# transponder_2018_v3.net
KiCad netlist of a schematic drawn in EAGLE
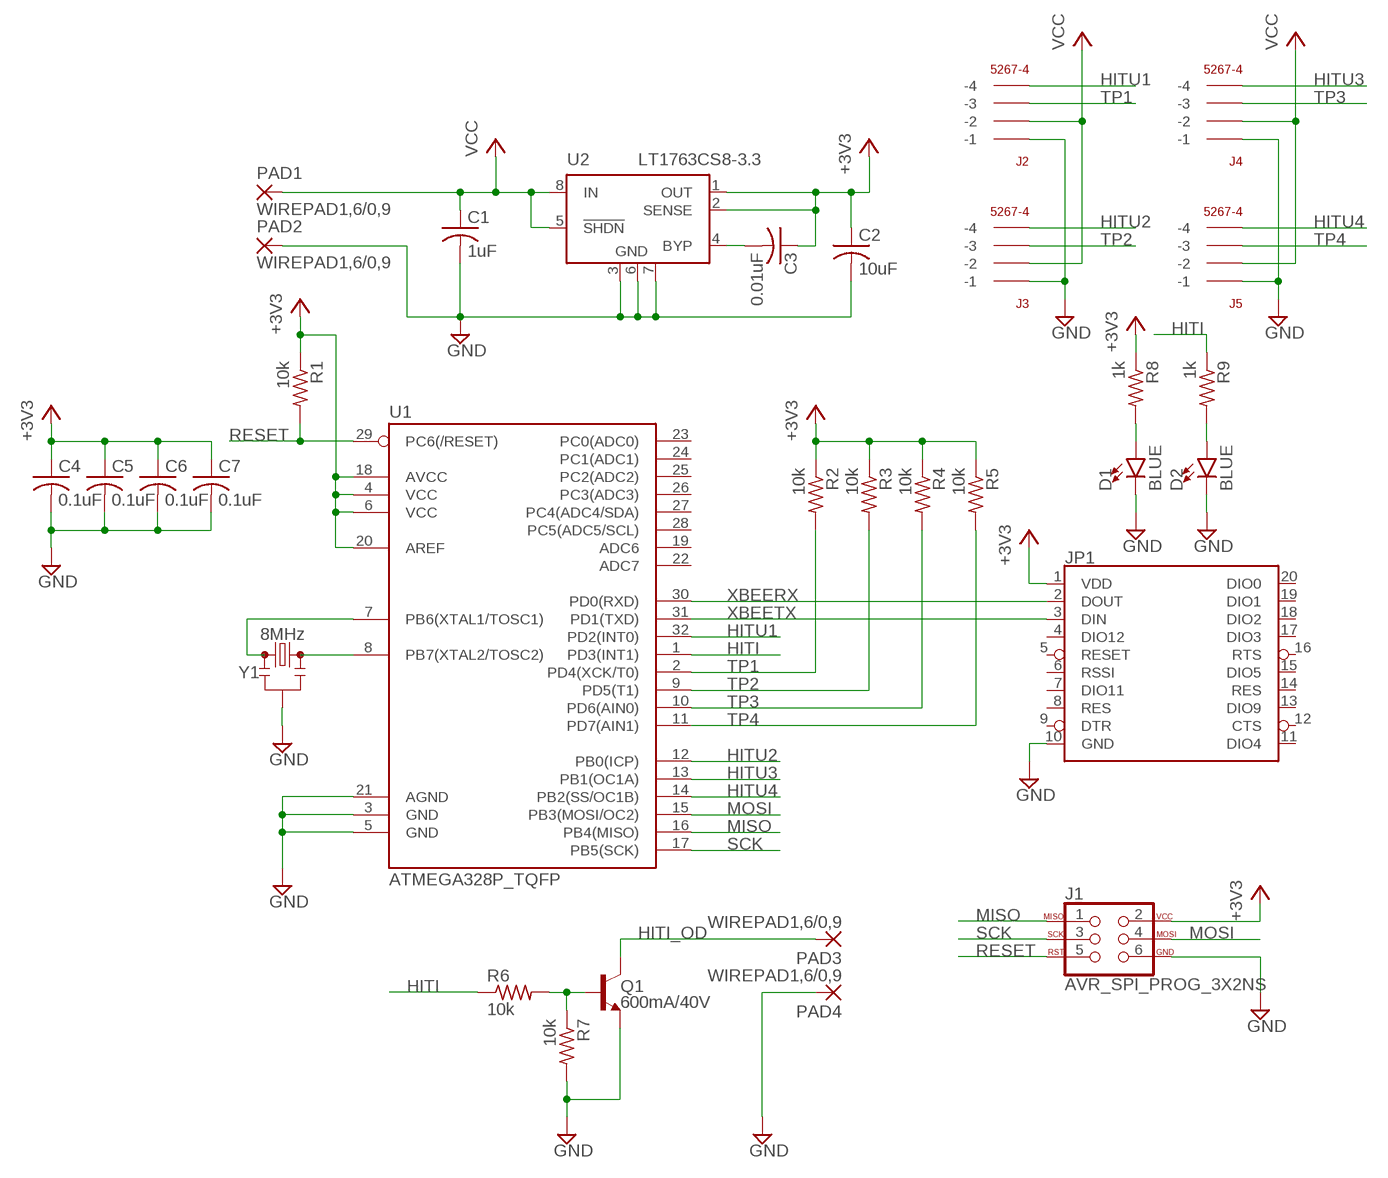
[diagram p0: schematic, sheet 1]

(export (version "E")
  (design (tool "Eeschema 10.0.6"))
  (components
    (comp (ref "C1")
      (value "1uF")
      (footprint "eagle-import:C0603")
      (libsource (lib "eagle-import") (part "C-USC0603"))
    )
    (comp (ref "C2")
      (value "10uF")
      (footprint "eagle-import:C1206")
      (libsource (lib "eagle-import") (part "C-USC1206"))
    )
    (comp (ref "C3")
      (value "0.01uF")
      (footprint "eagle-import:C0603")
      (libsource (lib "eagle-import") (part "C-USC0603"))
    )
    (comp (ref "C4")
      (value "0.1uF")
      (footprint "eagle-import:C0603")
      (libsource (lib "eagle-import") (part "C-USC0603"))
    )
    (comp (ref "C5")
      (value "0.1uF")
      (footprint "eagle-import:C0603")
      (libsource (lib "eagle-import") (part "C-USC0603"))
    )
    (comp (ref "C6")
      (value "0.1uF")
      (footprint "eagle-import:C0603")
      (libsource (lib "eagle-import") (part "C-USC0603"))
    )
    (comp (ref "C7")
      (value "0.1uF")
      (footprint "eagle-import:C0603")
      (libsource (lib "eagle-import") (part "C-USC0603"))
    )
    (comp (ref "D1")
      (value "BLUE")
      (footprint "eagle-import:LED-0603")
      (libsource (lib "eagle-import") (part "LED-BLUE0603"))
    )
    (comp (ref "D2")
      (value "BLUE")
      (footprint "eagle-import:LED-0603")
      (libsource (lib "eagle-import") (part "LED-BLUE0603"))
    )
    (comp (ref "J1")
      (value "AVR_SPI_PROG_3X2NS")
      (footprint "eagle-import:2X3-NS")
      (libsource (lib "eagle-import") (part "AVR_SPI_PROG_3X2NS"))
    )
    (comp (ref "J2")
      (value "5267-4")
      (footprint "eagle-import:5267-4")
      (libsource (lib "eagle-import") (part "5267-4"))
    )
    (comp (ref "J3")
      (value "5267-4")
      (footprint "eagle-import:5267-4")
      (libsource (lib "eagle-import") (part "5267-4"))
    )
    (comp (ref "J4")
      (value "5267-4")
      (footprint "eagle-import:5267-4")
      (libsource (lib "eagle-import") (part "5267-4"))
    )
    (comp (ref "J5")
      (value "5267-4")
      (footprint "eagle-import:5267-4")
      (libsource (lib "eagle-import") (part "5267-4"))
    )
    (comp (ref "JP1")
      (value "XBEESMD")
      (footprint "eagle-import:XBEE-SMD")
      (libsource (lib "eagle-import") (part "XBEESMD"))
    )
    (comp (ref "PAD1")
      (value "WIREPAD1,6/0,9")
      (footprint "eagle-import:1,6_0,9")
      (libsource (lib "eagle-import") (part "WIREPAD1,6/0,9"))
    )
    (comp (ref "PAD2")
      (value "WIREPAD1,6/0,9")
      (footprint "eagle-import:1,6_0,9")
      (libsource (lib "eagle-import") (part "WIREPAD1,6/0,9"))
    )
    (comp (ref "PAD3")
      (value "WIREPAD1,6/0,9")
      (footprint "eagle-import:1,6_0,9")
      (libsource (lib "eagle-import") (part "WIREPAD1,6/0,9"))
    )
    (comp (ref "PAD4")
      (value "WIREPAD1,6/0,9")
      (footprint "eagle-import:1,6_0,9")
      (libsource (lib "eagle-import") (part "WIREPAD1,6/0,9"))
    )
    (comp (ref "Q1")
      (value "600mA/40V")
      (footprint "eagle-import:SOT23-3")
      (libsource (lib "eagle-import") (part "TRANS_NPN-MMBT2222AL"))
    )
    (comp (ref "R1")
      (value "10k")
      (footprint "eagle-import:R0603")
      (libsource (lib "eagle-import") (part "R-US_R0603"))
    )
    (comp (ref "R2")
      (value "10k")
      (footprint "eagle-import:R0603")
      (libsource (lib "eagle-import") (part "R-US_R0603"))
    )
    (comp (ref "R3")
      (value "10k")
      (footprint "eagle-import:R0603")
      (libsource (lib "eagle-import") (part "R-US_R0603"))
    )
    (comp (ref "R4")
      (value "10k")
      (footprint "eagle-import:R0603")
      (libsource (lib "eagle-import") (part "R-US_R0603"))
    )
    (comp (ref "R5")
      (value "10k")
      (footprint "eagle-import:R0603")
      (libsource (lib "eagle-import") (part "R-US_R0603"))
    )
    (comp (ref "R6")
      (value "10k")
      (footprint "eagle-import:R0603")
      (libsource (lib "eagle-import") (part "R-US_R0603"))
    )
    (comp (ref "R7")
      (value "10k")
      (footprint "eagle-import:R0603")
      (libsource (lib "eagle-import") (part "R-US_R0603"))
    )
    (comp (ref "R8")
      (value "1k")
      (footprint "eagle-import:R0603")
      (libsource (lib "eagle-import") (part "R-US_R0603"))
    )
    (comp (ref "R9")
      (value "1k")
      (footprint "eagle-import:R0603")
      (libsource (lib "eagle-import") (part "R-US_R0603"))
    )
    (comp (ref "U1")
      (value "ATMEGA328P_TQFP")
      (footprint "eagle-import:TQFP32-08")
      (libsource (lib "eagle-import") (part "ATMEGA328P_TQFP"))
    )
    (comp (ref "U2")
      (value "LT1763CS8-3.3")
      (footprint "eagle-import:SOIC8")
      (libsource (lib "eagle-import") (part "LT1763CS8-3.3"))
    )
    (comp (ref "Y1")
      (value "8MHz")
      (footprint "eagle-import:RESONATOR-SMD-3.2X1.3")
      (libsource (lib "eagle-import") (part "RESONATOR-8MHZSMD_3.2X1.3"))
    )
  )
  (nets
    (net (code "1") (name "+3V3") (class "Default")
      (node (ref "C2") (pin "1") (pinfunction "1_1") (pintype "passive"))
      (node (ref "C3") (pin "1") (pinfunction "1_1") (pintype "passive"))
      (node (ref "C4") (pin "1") (pinfunction "1_1") (pintype "passive"))
      (node (ref "C5") (pin "1") (pinfunction "1_1") (pintype "passive"))
      (node (ref "C6") (pin "1") (pinfunction "1_1") (pintype "passive"))
      (node (ref "C7") (pin "1") (pinfunction "1_1") (pintype "passive"))
      (node (ref "J1") (pin "2") (pinfunction "2_2") (pintype "passive"))
      (node (ref "JP1") (pin "1") (pinfunction "VDD_1") (pintype "power_in"))
      (node (ref "R1") (pin "1") (pinfunction "1_1") (pintype "passive"))
      (node (ref "R2") (pin "1") (pinfunction "1_1") (pintype "passive"))
      (node (ref "R3") (pin "1") (pinfunction "1_1") (pintype "passive"))
      (node (ref "R4") (pin "1") (pinfunction "1_1") (pintype "passive"))
      (node (ref "R5") (pin "1") (pinfunction "1_1") (pintype "passive"))
      (node (ref "R8") (pin "1") (pinfunction "1_1") (pintype "passive"))
      (node (ref "U1") (pin "18") (pinfunction "AVCC_18") (pintype "bidirectional"))
      (node (ref "U1") (pin "20") (pinfunction "AREF_20") (pintype "bidirectional"))
      (node (ref "U1") (pin "4") (pinfunction "VCC_4") (pintype "bidirectional"))
      (node (ref "U1") (pin "6") (pinfunction "VCC_6") (pintype "bidirectional"))
      (node (ref "U2") (pin "1") (pinfunction "OUT_1") (pintype "passive"))
      (node (ref "U2") (pin "2") (pinfunction "SENSE_2") (pintype "input"))
    )
    (net (code "2") (name "/HITI") (class "Default")
      (node (ref "R6") (pin "1") (pinfunction "1_1") (pintype "passive"))
      (node (ref "R9") (pin "1") (pinfunction "1_1") (pintype "passive"))
      (node (ref "U1") (pin "1") (pinfunction "PD3(INT1)_1") (pintype "bidirectional"))
    )
    (net (code "3") (name "/HITI_OD") (class "Default")
      (node (ref "PAD3") (pin "1") (pinfunction "P_1") (pintype "passive"))
      (node (ref "Q1") (pin "3") (pinfunction "C_3") (pintype "passive"))
    )
    (net (code "4") (name "/HITU1") (class "Default")
      (node (ref "J2") (pin "P$4") (pinfunction "-4_P$4") (pintype "bidirectional"))
      (node (ref "U1") (pin "32") (pinfunction "PD2(INT0)_32") (pintype "bidirectional"))
    )
    (net (code "5") (name "/HITU2") (class "Default")
      (node (ref "J3") (pin "P$4") (pinfunction "-4_P$4") (pintype "bidirectional"))
      (node (ref "U1") (pin "12") (pinfunction "PB0(ICP)_12") (pintype "bidirectional"))
    )
    (net (code "6") (name "/HITU3") (class "Default")
      (node (ref "J4") (pin "P$4") (pinfunction "-4_P$4") (pintype "bidirectional"))
      (node (ref "U1") (pin "13") (pinfunction "PB1(OC1A)_13") (pintype "bidirectional"))
    )
    (net (code "7") (name "/HITU4") (class "Default")
      (node (ref "J5") (pin "P$4") (pinfunction "-4_P$4") (pintype "bidirectional"))
      (node (ref "U1") (pin "14") (pinfunction "PB2(SS/OC1B)_14") (pintype "bidirectional"))
    )
    (net (code "8") (name "/MISO") (class "Default")
      (node (ref "J1") (pin "1") (pinfunction "1_1") (pintype "passive"))
      (node (ref "U1") (pin "16") (pinfunction "PB4(MISO)_16") (pintype "bidirectional"))
    )
    (net (code "9") (name "/MOSI") (class "Default")
      (node (ref "J1") (pin "4") (pinfunction "4_4") (pintype "passive"))
      (node (ref "U1") (pin "15") (pinfunction "PB3(MOSI/OC2)_15") (pintype "bidirectional"))
    )
    (net (code "10") (name "/RESET") (class "Default")
      (node (ref "J1") (pin "5") (pinfunction "5_5") (pintype "passive"))
      (node (ref "R1") (pin "2") (pinfunction "2_2") (pintype "passive"))
      (node (ref "U1") (pin "29") (pinfunction "PC6(/RESET)_29") (pintype "bidirectional"))
    )
    (net (code "11") (name "/SCK") (class "Default")
      (node (ref "J1") (pin "3") (pinfunction "3_3") (pintype "passive"))
      (node (ref "U1") (pin "17") (pinfunction "PB5(SCK)_17") (pintype "bidirectional"))
    )
    (net (code "12") (name "/TP1") (class "Default")
      (node (ref "J2") (pin "P$3") (pinfunction "-3_P$3") (pintype "bidirectional"))
      (node (ref "R2") (pin "2") (pinfunction "2_2") (pintype "passive"))
      (node (ref "U1") (pin "2") (pinfunction "PD4(XCK/T0)_2") (pintype "bidirectional"))
    )
    (net (code "13") (name "/TP2") (class "Default")
      (node (ref "J3") (pin "P$3") (pinfunction "-3_P$3") (pintype "bidirectional"))
      (node (ref "R3") (pin "2") (pinfunction "2_2") (pintype "passive"))
      (node (ref "U1") (pin "9") (pinfunction "PD5(T1)_9") (pintype "bidirectional"))
    )
    (net (code "14") (name "/TP3") (class "Default")
      (node (ref "J4") (pin "P$3") (pinfunction "-3_P$3") (pintype "bidirectional"))
      (node (ref "R4") (pin "2") (pinfunction "2_2") (pintype "passive"))
      (node (ref "U1") (pin "10") (pinfunction "PD6(AIN0)_10") (pintype "bidirectional"))
    )
    (net (code "15") (name "/TP4") (class "Default")
      (node (ref "J5") (pin "P$3") (pinfunction "-3_P$3") (pintype "bidirectional"))
      (node (ref "R5") (pin "2") (pinfunction "2_2") (pintype "passive"))
      (node (ref "U1") (pin "11") (pinfunction "PD7(AIN1)_11") (pintype "bidirectional"))
    )
    (net (code "16") (name "/XBEERX") (class "Default")
      (node (ref "JP1") (pin "2") (pinfunction "DOUT_2") (pintype "output"))
      (node (ref "U1") (pin "30") (pinfunction "PD0(RXD)_30") (pintype "bidirectional"))
    )
    (net (code "17") (name "/XBEETX") (class "Default")
      (node (ref "JP1") (pin "3") (pinfunction "DIN_3") (pintype "input"))
      (node (ref "U1") (pin "31") (pinfunction "PD1(TXD)_31") (pintype "bidirectional"))
    )
    (net (code "18") (name "GND") (class "Default")
      (node (ref "C1") (pin "2") (pinfunction "2_2") (pintype "passive"))
      (node (ref "C2") (pin "2") (pinfunction "2_2") (pintype "passive"))
      (node (ref "C4") (pin "2") (pinfunction "2_2") (pintype "passive"))
      (node (ref "C5") (pin "2") (pinfunction "2_2") (pintype "passive"))
      (node (ref "C6") (pin "2") (pinfunction "2_2") (pintype "passive"))
      (node (ref "C7") (pin "2") (pinfunction "2_2") (pintype "passive"))
      (node (ref "D1") (pin "C") (pinfunction "C_C") (pintype "passive"))
      (node (ref "D2") (pin "C") (pinfunction "C_C") (pintype "passive"))
      (node (ref "J1") (pin "6") (pinfunction "6_6") (pintype "passive"))
      (node (ref "J2") (pin "P$1") (pinfunction "-1_P$1") (pintype "bidirectional"))
      (node (ref "J3") (pin "P$1") (pinfunction "-1_P$1") (pintype "bidirectional"))
      (node (ref "J4") (pin "P$1") (pinfunction "-1_P$1") (pintype "bidirectional"))
      (node (ref "J5") (pin "P$1") (pinfunction "-1_P$1") (pintype "bidirectional"))
      (node (ref "JP1") (pin "10") (pinfunction "GND_10") (pintype "power_in"))
      (node (ref "PAD2") (pin "1") (pinfunction "P_1") (pintype "passive"))
      (node (ref "PAD4") (pin "1") (pinfunction "P_1") (pintype "passive"))
      (node (ref "Q1") (pin "2") (pinfunction "E_2") (pintype "passive"))
      (node (ref "R7") (pin "2") (pinfunction "2_2") (pintype "passive"))
      (node (ref "U1") (pin "21") (pinfunction "AGND_21") (pintype "bidirectional"))
      (node (ref "U1") (pin "3") (pinfunction "GND_3") (pintype "bidirectional"))
      (node (ref "U1") (pin "5") (pinfunction "GND_5") (pintype "bidirectional"))
      (node (ref "U2") (pin "3") (pinfunction "GND_3") (pintype "power_in"))
      (node (ref "U2") (pin "6") (pinfunction "GND_6") (pintype "power_in"))
      (node (ref "U2") (pin "7") (pinfunction "GND_7") (pintype "power_in"))
      (node (ref "Y1") (pin "2") (pinfunction "2_2") (pintype "passive"))
    )
    (net (code "19") (name "Net-(D1-PadA)") (class "Default")
      (node (ref "D1") (pin "A") (pinfunction "A_A") (pintype "passive"))
      (node (ref "R8") (pin "2") (pinfunction "2_2") (pintype "passive"))
    )
    (net (code "20") (name "Net-(D2-PadA)") (class "Default")
      (node (ref "D2") (pin "A") (pinfunction "A_A") (pintype "passive"))
      (node (ref "R9") (pin "2") (pinfunction "2_2") (pintype "passive"))
    )
    (net (code "21") (name "Net-(Q1-B)") (class "Default")
      (node (ref "Q1") (pin "1") (pinfunction "B_1") (pintype "passive"))
      (node (ref "R6") (pin "2") (pinfunction "2_2") (pintype "passive"))
      (node (ref "R7") (pin "1") (pinfunction "1_1") (pintype "passive"))
    )
    (net (code "22") (name "Net-(U1-PB6(XTAL1{slash}TOSC1))") (class "Default")
      (node (ref "U1") (pin "7") (pinfunction "PB6(XTAL1/TOSC1)_7") (pintype "bidirectional"))
      (node (ref "Y1") (pin "1") (pinfunction "1_1") (pintype "passive"))
    )
    (net (code "23") (name "Net-(U1-PB7(XTAL2{slash}TOSC2))") (class "Default")
      (node (ref "U1") (pin "8") (pinfunction "PB7(XTAL2/TOSC2)_8") (pintype "bidirectional"))
      (node (ref "Y1") (pin "3") (pinfunction "3_3") (pintype "passive"))
    )
    (net (code "24") (name "Net-(U2-BYP)") (class "Default")
      (node (ref "C3") (pin "2") (pinfunction "2_2") (pintype "passive"))
      (node (ref "U2") (pin "4") (pinfunction "BYP_4") (pintype "input"))
    )
    (net (code "25") (name "VCC") (class "Default")
      (node (ref "C1") (pin "1") (pinfunction "1_1") (pintype "passive"))
      (node (ref "J2") (pin "P$2") (pinfunction "-2_P$2") (pintype "bidirectional"))
      (node (ref "J3") (pin "P$2") (pinfunction "-2_P$2") (pintype "bidirectional"))
      (node (ref "J4") (pin "P$2") (pinfunction "-2_P$2") (pintype "bidirectional"))
      (node (ref "J5") (pin "P$2") (pinfunction "-2_P$2") (pintype "bidirectional"))
      (node (ref "PAD1") (pin "1") (pinfunction "P_1") (pintype "passive"))
      (node (ref "U2") (pin "5") (pinfunction "~{SHDN}_5") (pintype "input"))
      (node (ref "U2") (pin "8") (pinfunction "IN_8") (pintype "input"))
    )
    (net (code "26") (name "unconnected-(JP1-CTS-Pad12)") (class "Default")
      (node (ref "JP1") (pin "12") (pinfunction "CTS_12") (pintype "output"))
    )
    (net (code "27") (name "unconnected-(JP1-DIO0-Pad20)") (class "Default")
      (node (ref "JP1") (pin "20") (pinfunction "DIO0_20") (pintype "bidirectional"))
    )
    (net (code "28") (name "unconnected-(JP1-DIO1-Pad19)") (class "Default")
      (node (ref "JP1") (pin "19") (pinfunction "DIO1_19") (pintype "bidirectional"))
    )
    (net (code "29") (name "unconnected-(JP1-DIO2-Pad18)") (class "Default")
      (node (ref "JP1") (pin "18") (pinfunction "DIO2_18") (pintype "bidirectional"))
    )
    (net (code "30") (name "unconnected-(JP1-DIO3-Pad17)") (class "Default")
      (node (ref "JP1") (pin "17") (pinfunction "DIO3_17") (pintype "bidirectional"))
    )
    (net (code "31") (name "unconnected-(JP1-DIO4-Pad11)") (class "Default")
      (node (ref "JP1") (pin "11") (pinfunction "DIO4_11") (pintype "bidirectional"))
    )
    (net (code "32") (name "unconnected-(JP1-DIO5-Pad15)") (class "Default")
      (node (ref "JP1") (pin "15") (pinfunction "DIO5_15") (pintype "bidirectional"))
    )
    (net (code "33") (name "unconnected-(JP1-DIO9-Pad13)") (class "Default")
      (node (ref "JP1") (pin "13") (pinfunction "DIO9_13") (pintype "bidirectional"))
    )
    (net (code "34") (name "unconnected-(JP1-DIO11-Pad7)") (class "Default")
      (node (ref "JP1") (pin "7") (pinfunction "DIO11_7") (pintype "bidirectional"))
    )
    (net (code "35") (name "unconnected-(JP1-DIO12-Pad4)") (class "Default")
      (node (ref "JP1") (pin "4") (pinfunction "DIO12_4") (pintype "bidirectional"))
    )
    (net (code "36") (name "unconnected-(JP1-DTR-Pad9)") (class "Default")
      (node (ref "JP1") (pin "9") (pinfunction "DTR_9") (pintype "bidirectional"))
    )
    (net (code "37") (name "unconnected-(JP1-RES-Pad8)") (class "Default")
      (node (ref "JP1") (pin "8") (pinfunction "RES_8") (pintype "bidirectional"))
    )
    (net (code "38") (name "unconnected-(JP1-RES-Pad14)") (class "Default")
      (node (ref "JP1") (pin "14") (pinfunction "RES_14") (pintype "bidirectional"))
    )
    (net (code "39") (name "unconnected-(JP1-RESET-Pad5)") (class "Default")
      (node (ref "JP1") (pin "5") (pinfunction "RESET_5") (pintype "input"))
    )
    (net (code "40") (name "unconnected-(JP1-RSSI-Pad6)") (class "Default")
      (node (ref "JP1") (pin "6") (pinfunction "RSSI_6") (pintype "bidirectional"))
    )
    (net (code "41") (name "unconnected-(JP1-RTS-Pad16)") (class "Default")
      (node (ref "JP1") (pin "16") (pinfunction "RTS_16") (pintype "input"))
    )
    (net (code "42") (name "unconnected-(U1-ADC6-Pad19)") (class "Default")
      (node (ref "U1") (pin "19") (pinfunction "ADC6_19") (pintype "bidirectional"))
    )
    (net (code "43") (name "unconnected-(U1-ADC7-Pad22)") (class "Default")
      (node (ref "U1") (pin "22") (pinfunction "ADC7_22") (pintype "bidirectional"))
    )
    (net (code "44") (name "unconnected-(U1-PC0(ADC0)-Pad23)") (class "Default")
      (node (ref "U1") (pin "23") (pinfunction "PC0(ADC0)_23") (pintype "bidirectional"))
    )
    (net (code "45") (name "unconnected-(U1-PC1(ADC1)-Pad24)") (class "Default")
      (node (ref "U1") (pin "24") (pinfunction "PC1(ADC1)_24") (pintype "bidirectional"))
    )
    (net (code "46") (name "unconnected-(U1-PC2(ADC2)-Pad25)") (class "Default")
      (node (ref "U1") (pin "25") (pinfunction "PC2(ADC2)_25") (pintype "bidirectional"))
    )
    (net (code "47") (name "unconnected-(U1-PC3(ADC3)-Pad26)") (class "Default")
      (node (ref "U1") (pin "26") (pinfunction "PC3(ADC3)_26") (pintype "bidirectional"))
    )
    (net (code "48") (name "unconnected-(U1-PC4(ADC4{slash}SDA)-Pad27)") (class "Default")
      (node (ref "U1") (pin "27") (pinfunction "PC4(ADC4/SDA)_27") (pintype "bidirectional"))
    )
    (net (code "49") (name "unconnected-(U1-PC5(ADC5{slash}SCL)-Pad28)") (class "Default")
      (node (ref "U1") (pin "28") (pinfunction "PC5(ADC5/SCL)_28") (pintype "bidirectional"))
    )
  )
)
